# CPU.net
KiCad netlist of a schematic drawn in Altium Designer
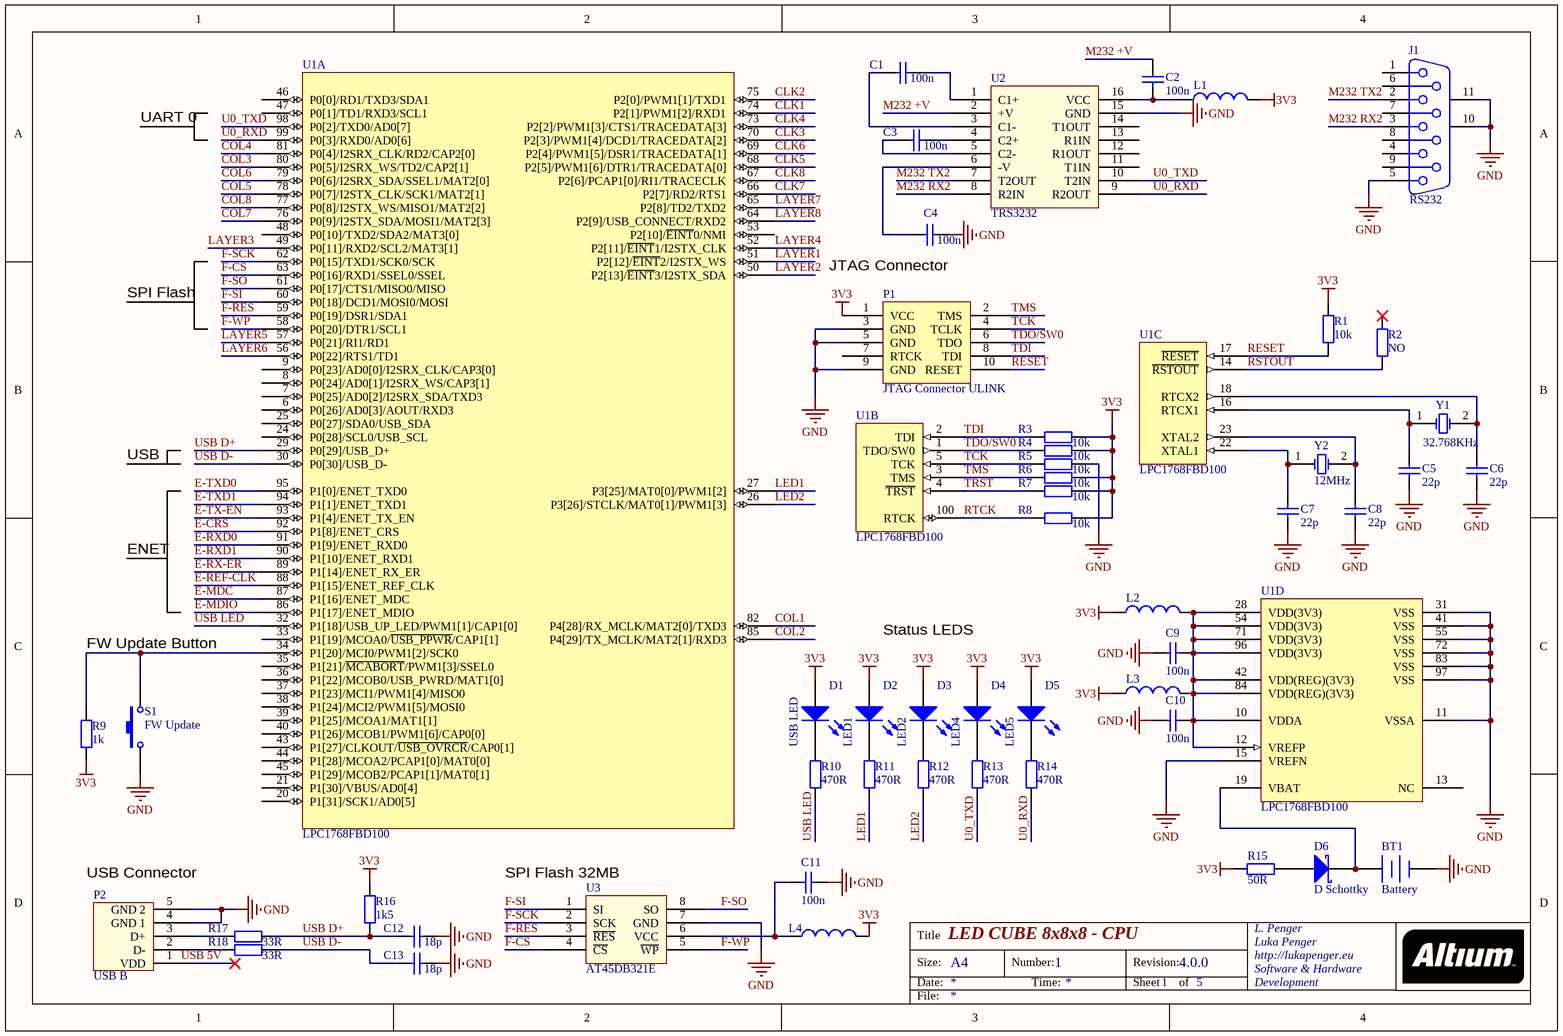
[diagram p0: CPU.SchDoc]

(export (version "E")
  (design (tool "Eeschema 10.0.6"))
  (components
    (comp (ref "BT1")
      (value "Battery")
      (footprint "Battery capacitor")
      (description "Multicell Battery")
      (fields (field (name "PUBLISHER") "Altium Limited"))
      (libsource (lib "Miscellaneous Devices") (part "Battery"))
    )
    (comp (ref "C1")
      (value "100n")
      (footprint "1608[0603]")
      (description "Capacitor")
      (fields (field (name "PUBLISHER") "Altium Limited"))
      (libsource (lib "Miscellaneous Devices") (part "Cap"))
    )
    (comp (ref "C2")
      (value "100n")
      (footprint "1608[0603]")
      (description "Capacitor")
      (fields (field (name "PUBLISHER") "Altium Limited"))
      (libsource (lib "Miscellaneous Devices") (part "Cap"))
    )
    (comp (ref "C3")
      (value "100n")
      (footprint "1608[0603]")
      (description "Capacitor")
      (fields (field (name "PUBLISHER") "Altium Limited"))
      (libsource (lib "Miscellaneous Devices") (part "Cap"))
    )
    (comp (ref "C4")
      (value "100n")
      (footprint "1608[0603]")
      (description "Capacitor")
      (fields (field (name "PUBLISHER") "Altium Limited"))
      (libsource (lib "Miscellaneous Devices") (part "Cap"))
    )
    (comp (ref "C5")
      (value "22p")
      (footprint "1608[0603]")
      (description "Capacitor")
      (fields (field (name "PUBLISHER") "Altium Limited"))
      (libsource (lib "Miscellaneous Devices") (part "Cap"))
    )
    (comp (ref "C6")
      (value "22p")
      (footprint "1608[0603]")
      (description "Capacitor")
      (fields (field (name "PUBLISHER") "Altium Limited"))
      (libsource (lib "Miscellaneous Devices") (part "Cap"))
    )
    (comp (ref "C7")
      (value "22p")
      (footprint "1608[0603]")
      (description "Capacitor")
      (fields (field (name "PUBLISHER") "Altium Limited"))
      (libsource (lib "Miscellaneous Devices") (part "Cap"))
    )
    (comp (ref "C8")
      (value "22p")
      (footprint "1608[0603]")
      (description "Capacitor")
      (fields (field (name "PUBLISHER") "Altium Limited"))
      (libsource (lib "Miscellaneous Devices") (part "Cap"))
    )
    (comp (ref "C9")
      (value "100n")
      (footprint "1608[0603]")
      (description "Capacitor")
      (fields (field (name "PUBLISHER") "Altium Limited"))
      (libsource (lib "Miscellaneous Devices") (part "Cap"))
    )
    (comp (ref "C10")
      (value "100n")
      (footprint "1608[0603]")
      (description "Capacitor")
      (fields (field (name "PUBLISHER") "Altium Limited"))
      (libsource (lib "Miscellaneous Devices") (part "Cap"))
    )
    (comp (ref "C11")
      (value "100n")
      (footprint "1608[0603]")
      (description "Capacitor")
      (fields (field (name "PUBLISHER") "Altium Limited"))
      (libsource (lib "Miscellaneous Devices") (part "Cap"))
    )
    (comp (ref "C12")
      (value "18p")
      (footprint "1608[0603]")
      (description "Capacitor")
      (fields (field (name "PUBLISHER") "Altium Limited"))
      (libsource (lib "Miscellaneous Devices") (part "Cap"))
    )
    (comp (ref "C13")
      (value "18p")
      (footprint "1608[0603]")
      (description "Capacitor")
      (fields (field (name "PUBLISHER") "Altium Limited"))
      (libsource (lib "Miscellaneous Devices") (part "Cap"))
    )
    (comp (ref "D1")
      (value "USB LED")
      (footprint "LED-1")
      (description "Typical INFRARED GaAs LED")
      (fields (field (name "PUBLISHER") "Altium Limited"))
      (libsource (lib "Miscellaneous Devices") (part "LED0"))
    )
    (comp (ref "D2")
      (value "LED1")
      (footprint "LED-1")
      (description "Typical INFRARED GaAs LED")
      (fields (field (name "PUBLISHER") "Altium Limited"))
      (libsource (lib "Miscellaneous Devices") (part "LED0"))
    )
    (comp (ref "D3")
      (value "LED2")
      (footprint "LED-1")
      (description "Typical INFRARED GaAs LED")
      (fields (field (name "PUBLISHER") "Altium Limited"))
      (libsource (lib "Miscellaneous Devices") (part "LED0"))
    )
    (comp (ref "D4")
      (value "LED4")
      (footprint "LED-1")
      (description "Typical INFRARED GaAs LED")
      (fields (field (name "PUBLISHER") "Altium Limited"))
      (libsource (lib "Miscellaneous Devices") (part "LED0"))
    )
    (comp (ref "D5")
      (value "LED5")
      (footprint "LED-1")
      (description "Typical INFRARED GaAs LED")
      (fields (field (name "PUBLISHER") "Altium Limited"))
      (libsource (lib "Miscellaneous Devices") (part "LED0"))
    )
    (comp (ref "D6")
      (value "D Schottky")
      (footprint "SMB")
      (description "Schottky Diode")
      (fields (field (name "PUBLISHER") "Altium Limited"))
      (libsource (lib "Miscellaneous Devices") (part "D Schottky"))
    )
    (comp (ref "J1")
      (value "RS232")
      (footprint "DSUB1.385-2H9")
      (description "Receptacle Assembly, 9 Position, Right Angle")
      (fields (field (name "PUBLISHER") "Altium Limited"))
      (libsource (lib "Miscellaneous Connectors") (part "D Connector 9"))
    )
    (comp (ref "L1")
      (value "Inductor")
      (footprint "1608[0603]")
      (fields (field (name "PUBLISHER") "Altium Limited"))
      (libsource (lib "Miscellaneous Devices") (part "Inductor"))
    )
    (comp (ref "L2")
      (value "Inductor")
      (footprint "1608[0603]")
      (fields (field (name "PUBLISHER") "Altium Limited"))
      (libsource (lib "Miscellaneous Devices") (part "Inductor"))
    )
    (comp (ref "L3")
      (value "Inductor")
      (footprint "1608[0603]")
      (fields (field (name "PUBLISHER") "Altium Limited"))
      (libsource (lib "Miscellaneous Devices") (part "Inductor"))
    )
    (comp (ref "L4")
      (value "Inductor")
      (footprint "1608[0603]")
      (fields (field (name "PUBLISHER") "Altium Limited"))
      (libsource (lib "Miscellaneous Devices") (part "Inductor"))
    )
    (comp (ref "P1")
      (value "JTAG Connector ULINK")
      (footprint "JTAG Connector ULINK")
      (description "JTAG Connector")
      (libsource (lib "LP_Lib") (part "JTAG Connector ULINK"))
    )
    (comp (ref "P2")
      (value "USB B")
      (footprint "USB B")
      (description "USB Connector")
      (libsource (lib "LP_Lib") (part "USB B"))
    )
    (comp (ref "R1")
      (value "10k")
      (footprint "1608[0603]")
      (description "Resistor")
      (fields (field (name "PUBLISHER") "Altium Limited"))
      (libsource (lib "Miscellaneous Devices") (part "Res2"))
    )
    (comp (ref "R2")
      (value "NO")
      (footprint "1608[0603]")
      (description "Resistor")
      (fields (field (name "PUBLISHER") "Altium Limited"))
      (libsource (lib "Miscellaneous Devices") (part "Res2"))
    )
    (comp (ref "R3")
      (value "10k")
      (footprint "1608[0603]")
      (description "Resistor")
      (fields (field (name "PUBLISHER") "Altium Limited"))
      (libsource (lib "") (part "Res2_3"))
    )
    (comp (ref "R4")
      (value "10k")
      (footprint "1608[0603]")
      (description "Resistor")
      (fields (field (name "PUBLISHER") "Altium Limited"))
      (libsource (lib "") (part "Res2_3"))
    )
    (comp (ref "R5")
      (value "10k")
      (footprint "1608[0603]")
      (description "Resistor")
      (fields (field (name "PUBLISHER") "Altium Limited"))
      (libsource (lib "") (part "Res2_3"))
    )
    (comp (ref "R6")
      (value "10k")
      (footprint "1608[0603]")
      (description "Resistor")
      (fields (field (name "PUBLISHER") "Altium Limited"))
      (libsource (lib "") (part "Res2_3"))
    )
    (comp (ref "R7")
      (value "10k")
      (footprint "1608[0603]")
      (description "Resistor")
      (fields (field (name "PUBLISHER") "Altium Limited"))
      (libsource (lib "") (part "Res2_3"))
    )
    (comp (ref "R8")
      (value "10k")
      (footprint "1608[0603]")
      (description "Resistor")
      (fields (field (name "PUBLISHER") "Altium Limited"))
      (libsource (lib "") (part "Res2_3"))
    )
    (comp (ref "R9")
      (value "1k")
      (footprint "1608[0603]")
      (description "Resistor")
      (fields (field (name "PUBLISHER") "Altium Limited"))
      (libsource (lib "Miscellaneous Devices") (part "Res2"))
    )
    (comp (ref "R10")
      (value "470R")
      (footprint "1608[0603]")
      (description "Resistor")
      (fields (field (name "PUBLISHER") "Altium Limited"))
      (libsource (lib "Miscellaneous Devices") (part "Res2"))
    )
    (comp (ref "R11")
      (value "470R")
      (footprint "1608[0603]")
      (description "Resistor")
      (fields (field (name "PUBLISHER") "Altium Limited"))
      (libsource (lib "Miscellaneous Devices") (part "Res2"))
    )
    (comp (ref "R12")
      (value "470R")
      (footprint "1608[0603]")
      (description "Resistor")
      (fields (field (name "PUBLISHER") "Altium Limited"))
      (libsource (lib "Miscellaneous Devices") (part "Res2"))
    )
    (comp (ref "R13")
      (value "470R")
      (footprint "1608[0603]")
      (description "Resistor")
      (fields (field (name "PUBLISHER") "Altium Limited"))
      (libsource (lib "Miscellaneous Devices") (part "Res2"))
    )
    (comp (ref "R14")
      (value "470R")
      (footprint "1608[0603]")
      (description "Resistor")
      (fields (field (name "PUBLISHER") "Altium Limited"))
      (libsource (lib "Miscellaneous Devices") (part "Res2"))
    )
    (comp (ref "R15")
      (value "50R")
      (footprint "6-0805_N")
      (description "Resistor")
      (fields (field (name "PUBLISHER") "Altium Limited"))
      (libsource (lib "") (part "Res2_1"))
    )
    (comp (ref "R16")
      (value "1k5")
      (footprint "1608[0603]")
      (description "Resistor")
      (fields (field (name "PUBLISHER") "Altium Limited"))
      (libsource (lib "") (part "Res2_2"))
    )
    (comp (ref "R17")
      (value "33R")
      (footprint "1608[0603]")
      (description "Resistor")
      (fields (field (name "PUBLISHER") "Altium Limited"))
      (libsource (lib "") (part "Res2_1"))
    )
    (comp (ref "R18")
      (value "33R")
      (footprint "1608[0603]")
      (description "Resistor")
      (fields (field (name "PUBLISHER") "Altium Limited"))
      (libsource (lib "") (part "Res2_1"))
    )
    (comp (ref "S1")
      (value "FW Update")
      (footprint "SWITCH-TACTILE-90")
      (description "Switch")
      (fields (field (name "PUBLISHER") "Altium Limited"))
      (libsource (lib "Miscellaneous Devices") (part "SW-PB"))
    )
    (comp (ref "U1")
      (value "LPC1768FBD100")
      (footprint "SOT407-1_N")
      (fields (field (name "PUBLISHER") "Altium Limited"))
      (libsource (lib "NXP LPC1768") (part "LPC1768FBD100"))
    )
    (comp (ref "U2")
      (value "TRS3232")
      (footprint "SOIC16_N")
      (description "Dual 232 +3V3")
      (libsource (lib "LP_Lib") (part "MAX2232"))
    )
    (comp (ref "U3")
      (value "AT45DB321E")
      (footprint "AT45DB321D")
      (description "SPI Flash 32MB")
      (libsource (lib "LP_Lib") (part "AT45DB321D"))
    )
    (comp (ref "Y1")
      (value "32.768KHz")
      (footprint "Crystal 4.1x1.5")
      (description "Crystal Oscillator")
      (fields (field (name "PUBLISHER") "Altium Limited"))
      (libsource (lib "Miscellaneous Devices") (part "XTAL"))
    )
    (comp (ref "Y2")
      (value "12MHz")
      (footprint "5x3.2 Crystal")
      (description "Crystal Oscillator")
      (fields (field (name "PUBLISHER") "Altium Limited"))
      (libsource (lib "Miscellaneous Devices") (part "XTAL"))
    )
  )
  (nets
    (net (code "1") (name "/CLK1") (class "Default")
      (node (ref "U1") (pin "74") (pinfunction "P2[1]/PWM1[2]/RXD1_74") (pintype "bidirectional"))
    )
    (net (code "2") (name "/CLK2") (class "Default")
      (node (ref "U1") (pin "75") (pinfunction "P2[0]/PWM1[1]/TXD1_75") (pintype "bidirectional"))
    )
    (net (code "3") (name "/CLK3") (class "Default")
      (node (ref "U1") (pin "70") (pinfunction "P2[3]/PWM1[4]/DCD1/TRACEDATA[2]_70") (pintype "bidirectional"))
    )
    (net (code "4") (name "/CLK4") (class "Default")
      (node (ref "U1") (pin "73") (pinfunction "P2[2]/PWM1[3]/CTS1/TRACEDATA[3]_73") (pintype "bidirectional"))
    )
    (net (code "5") (name "/CLK5") (class "Default")
      (node (ref "U1") (pin "68") (pinfunction "P2[5]/PWM1[6]/DTR1/TRACEDATA[0]_68") (pintype "bidirectional"))
    )
    (net (code "6") (name "/CLK6") (class "Default")
      (node (ref "U1") (pin "69") (pinfunction "P2[4]/PWM1[5]/DSR1/TRACEDATA[1]_69") (pintype "bidirectional"))
    )
    (net (code "7") (name "/CLK7") (class "Default")
      (node (ref "U1") (pin "66") (pinfunction "P2[7]/RD2/RTS1_66") (pintype "bidirectional"))
    )
    (net (code "8") (name "/CLK8") (class "Default")
      (node (ref "U1") (pin "67") (pinfunction "P2[6]/PCAP1[0]/RI1/TRACECLK_67") (pintype "bidirectional"))
    )
    (net (code "9") (name "/COL1") (class "Default")
      (node (ref "U1") (pin "82") (pinfunction "P4[28]/RX_MCLK/MAT2[0]/TXD3_82") (pintype "bidirectional"))
    )
    (net (code "10") (name "/COL2") (class "Default")
      (node (ref "U1") (pin "85") (pinfunction "P4[29]/TX_MCLK/MAT2[1]/RXD3_85") (pintype "bidirectional"))
    )
    (net (code "11") (name "/COL3") (class "Default")
      (node (ref "U1") (pin "80") (pinfunction "P0[5]/I2SRX_WS/TD2/CAP2[1]_80") (pintype "bidirectional"))
    )
    (net (code "12") (name "/COL4") (class "Default")
      (node (ref "U1") (pin "81") (pinfunction "P0[4]/I2SRX_CLK/RD2/CAP2[0]_81") (pintype "bidirectional"))
    )
    (net (code "13") (name "/COL5") (class "Default")
      (node (ref "U1") (pin "78") (pinfunction "P0[7]/I2STX_CLK/SCK1/MAT2[1]_78") (pintype "bidirectional"))
    )
    (net (code "14") (name "/COL6") (class "Default")
      (node (ref "U1") (pin "79") (pinfunction "P0[6]/I2SRX_SDA/SSEL1/MAT2[0]_79") (pintype "bidirectional"))
    )
    (net (code "15") (name "/COL7") (class "Default")
      (node (ref "U1") (pin "76") (pinfunction "P0[9]/I2STX_SDA/MOSI1/MAT2[3]_76") (pintype "bidirectional"))
    )
    (net (code "16") (name "/COL8") (class "Default")
      (node (ref "U1") (pin "77") (pinfunction "P0[8]/I2STX_WS/MISO1/MAT2[2]_77") (pintype "bidirectional"))
    )
    (net (code "17") (name "/E-CRS") (class "Default")
      (node (ref "U1") (pin "92") (pinfunction "P1[8]/ENET_CRS_92") (pintype "bidirectional"))
    )
    (net (code "18") (name "/E-MDC") (class "Default")
      (node (ref "U1") (pin "87") (pinfunction "P1[16]/ENET_MDC_87") (pintype "bidirectional"))
    )
    (net (code "19") (name "/E-MDIO") (class "Default")
      (node (ref "U1") (pin "86") (pinfunction "P1[17]/ENET_MDIO_86") (pintype "bidirectional"))
    )
    (net (code "20") (name "/E-REF-CLK") (class "Default")
      (node (ref "U1") (pin "88") (pinfunction "P1[15]/ENET_REF_CLK_88") (pintype "bidirectional"))
    )
    (net (code "21") (name "/E-RX-ER") (class "Default")
      (node (ref "U1") (pin "89") (pinfunction "P1[14]/ENET_RX_ER_89") (pintype "bidirectional"))
    )
    (net (code "22") (name "/E-RXD0") (class "Default")
      (node (ref "U1") (pin "91") (pinfunction "P1[9]/ENET_RXD0_91") (pintype "bidirectional"))
    )
    (net (code "23") (name "/E-RXD1") (class "Default")
      (node (ref "U1") (pin "90") (pinfunction "P1[10]/ENET_RXD1_90") (pintype "bidirectional"))
    )
    (net (code "24") (name "/E-TX-EN") (class "Default")
      (node (ref "U1") (pin "93") (pinfunction "P1[4]/ENET_TX_EN_93") (pintype "bidirectional"))
    )
    (net (code "25") (name "/E-TXD0") (class "Default")
      (node (ref "U1") (pin "95") (pinfunction "P1[0]/ENET_TXD0_95") (pintype "bidirectional"))
    )
    (net (code "26") (name "/E-TXD1") (class "Default")
      (node (ref "U1") (pin "94") (pinfunction "P1[1]/ENET_TXD1_94") (pintype "bidirectional"))
    )
    (net (code "27") (name "/F-CS") (class "Default")
      (node (ref "U1") (pin "63") (pinfunction "P0[16]/RXD1/SSEL0/SSEL_63") (pintype "bidirectional"))
      (node (ref "U3") (pin "4") (pinfunction "~{CS}_4") (pintype "passive"))
    )
    (net (code "28") (name "/F-RES") (class "Default")
      (node (ref "U1") (pin "59") (pinfunction "P0[19]/DSR1/SDA1_59") (pintype "bidirectional"))
      (node (ref "U3") (pin "3") (pinfunction "~{RES}_3") (pintype "passive"))
    )
    (net (code "29") (name "/F-SCK") (class "Default")
      (node (ref "U1") (pin "62") (pinfunction "P0[15]/TXD1/SCK0/SCK_62") (pintype "bidirectional"))
      (node (ref "U3") (pin "2") (pinfunction "SCK_2") (pintype "passive"))
    )
    (net (code "30") (name "/F-SI") (class "Default")
      (node (ref "U1") (pin "60") (pinfunction "P0[18]/DCD1/MOSI0/MOSI_60") (pintype "bidirectional"))
      (node (ref "U3") (pin "1") (pinfunction "SI_1") (pintype "passive"))
    )
    (net (code "31") (name "/F-SO") (class "Default")
      (node (ref "U1") (pin "61") (pinfunction "P0[17]/CTS1/MISO0/MISO_61") (pintype "bidirectional"))
      (node (ref "U3") (pin "8") (pinfunction "SO_8") (pintype "passive"))
    )
    (net (code "32") (name "/F-WP") (class "Default")
      (node (ref "U1") (pin "58") (pinfunction "P0[20]/DTR1/SCL1_58") (pintype "bidirectional"))
      (node (ref "U3") (pin "5") (pinfunction "~{WP}_5") (pintype "passive"))
    )
    (net (code "33") (name "/LAYER1") (class "Default")
      (node (ref "U1") (pin "51") (pinfunction "P2[12]/~{EINT}2/I2STX_WS_51") (pintype "bidirectional"))
    )
    (net (code "34") (name "/LAYER2") (class "Default")
      (node (ref "U1") (pin "50") (pinfunction "P2[13]/~{EINT}3/I2STX_SDA_50") (pintype "bidirectional"))
    )
    (net (code "35") (name "/LAYER3") (class "Default")
      (node (ref "U1") (pin "49") (pinfunction "P0[11]/RXD2/SCL2/MAT3[1]_49") (pintype "bidirectional"))
    )
    (net (code "36") (name "/LAYER4") (class "Default")
      (node (ref "U1") (pin "52") (pinfunction "P2[11]/~{EINT}1/I2STX_CLK_52") (pintype "bidirectional"))
    )
    (net (code "37") (name "/LAYER5") (class "Default")
      (node (ref "U1") (pin "57") (pinfunction "P0[21]/RI1/RD1_57") (pintype "bidirectional"))
    )
    (net (code "38") (name "/LAYER6") (class "Default")
      (node (ref "U1") (pin "56") (pinfunction "P0[22]/RTS1/TD1_56") (pintype "bidirectional"))
    )
    (net (code "39") (name "/LAYER7") (class "Default")
      (node (ref "U1") (pin "65") (pinfunction "P2[8]/TD2/TXD2_65") (pintype "bidirectional"))
    )
    (net (code "40") (name "/LAYER8") (class "Default")
      (node (ref "U1") (pin "64") (pinfunction "P2[9]/USB_CONNECT/RXD2_64") (pintype "bidirectional"))
    )
    (net (code "41") (name "/LED1") (class "Default")
      (node (ref "R11") (pin "1") (pinfunction "1_1") (pintype "passive"))
      (node (ref "U1") (pin "27") (pinfunction "P3[25]/MAT0[0]/PWM1[2]_27") (pintype "bidirectional"))
    )
    (net (code "42") (name "/LED2") (class "Default")
      (node (ref "R12") (pin "1") (pinfunction "1_1") (pintype "passive"))
      (node (ref "U1") (pin "26") (pinfunction "P3[26]/STCLK/MAT0[1]/PWM1[3]_26") (pintype "bidirectional"))
    )
    (net (code "43") (name "/M232 +V") (class "Default")
      (node (ref "C2") (pin "1") (pinfunction "1_1") (pintype "passive"))
      (node (ref "U2") (pin "2") (pinfunction "+V_2") (pintype "passive"))
    )
    (net (code "44") (name "/M232 RX2") (class "Default")
      (node (ref "J1") (pin "3") (pinfunction "3_3") (pintype "passive"))
      (node (ref "U2") (pin "8") (pinfunction "R2IN_8") (pintype "passive"))
    )
    (net (code "45") (name "/M232 TX2") (class "Default")
      (node (ref "J1") (pin "2") (pinfunction "2_2") (pintype "passive"))
      (node (ref "U2") (pin "7") (pinfunction "T2OUT_7") (pintype "passive"))
    )
    (net (code "46") (name "/RESET") (class "Default")
      (node (ref "P1") (pin "10") (pinfunction "RESET_10") (pintype "passive"))
      (node (ref "R1") (pin "1") (pinfunction "1_1") (pintype "passive"))
      (node (ref "U1") (pin "17") (pinfunction "~{RESET}_17") (pintype "input"))
    )
    (net (code "47") (name "/RSTOUT") (class "Default")
      (node (ref "R2") (pin "1") (pinfunction "1_1") (pintype "passive"))
      (node (ref "U1") (pin "14") (pinfunction "~{RSTOUT}_14") (pintype "output"))
    )
    (net (code "48") (name "/RTCK") (class "Default")
      (node (ref "R8") (pin "1") (pinfunction "1_1") (pintype "passive"))
      (node (ref "U1") (pin "100") (pinfunction "RTCK_100") (pintype "bidirectional"))
    )
    (net (code "49") (name "/TCK") (class "Default")
      (node (ref "P1") (pin "4") (pinfunction "TCLK_4") (pintype "passive"))
      (node (ref "R5") (pin "1") (pinfunction "1_1") (pintype "passive"))
      (node (ref "U1") (pin "5") (pinfunction "TCK_5") (pintype "input"))
    )
    (net (code "50") (name "/TDI") (class "Default")
      (node (ref "P1") (pin "8") (pinfunction "TDI_8") (pintype "passive"))
      (node (ref "R3") (pin "1") (pinfunction "1_1") (pintype "passive"))
      (node (ref "U1") (pin "2") (pinfunction "TDI_2") (pintype "input"))
    )
    (net (code "51") (name "/TDO{slash}SW0") (class "Default")
      (node (ref "P1") (pin "6") (pinfunction "TDO_6") (pintype "passive"))
      (node (ref "R4") (pin "1") (pinfunction "1_1") (pintype "passive"))
      (node (ref "U1") (pin "1") (pinfunction "TDO/SW0_1") (pintype "output"))
    )
    (net (code "52") (name "/TMS") (class "Default")
      (node (ref "P1") (pin "2") (pinfunction "TMS_2") (pintype "passive"))
      (node (ref "R6") (pin "1") (pinfunction "1_1") (pintype "passive"))
      (node (ref "U1") (pin "3") (pinfunction "TMS_3") (pintype "input"))
    )
    (net (code "53") (name "/TRST") (class "Default")
      (node (ref "R7") (pin "1") (pinfunction "1_1") (pintype "passive"))
      (node (ref "U1") (pin "4") (pinfunction "~{TRST}_4") (pintype "input"))
    )
    (net (code "54") (name "/U0_RXD") (class "Default")
      (node (ref "R14") (pin "1") (pinfunction "1_1") (pintype "passive"))
      (node (ref "U1") (pin "99") (pinfunction "P0[3]/RXD0/AD0[6]_99") (pintype "bidirectional"))
      (node (ref "U2") (pin "9") (pinfunction "R2OUT_9") (pintype "passive"))
    )
    (net (code "55") (name "/U0_TXD") (class "Default")
      (node (ref "R13") (pin "1") (pinfunction "1_1") (pintype "passive"))
      (node (ref "U1") (pin "98") (pinfunction "P0[2]/TXD0/AD0[7]_98") (pintype "bidirectional"))
      (node (ref "U2") (pin "10") (pinfunction "T2IN_10") (pintype "passive"))
    )
    (net (code "57") (name "/USB D+") (class "Default")
      (node (ref "C12") (pin "1") (pinfunction "1_1") (pintype "passive"))
      (node (ref "R16") (pin "2") (pinfunction "2_2") (pintype "passive"))
      (node (ref "R17") (pin "1") (pinfunction "1_1") (pintype "passive"))
      (node (ref "U1") (pin "29") (pinfunction "P0[29]/USB_D+_29") (pintype "bidirectional"))
    )
    (net (code "58") (name "/USB D-") (class "Default")
      (node (ref "C13") (pin "1") (pinfunction "1_1") (pintype "passive"))
      (node (ref "R18") (pin "1") (pinfunction "1_1") (pintype "passive"))
      (node (ref "U1") (pin "30") (pinfunction "P0[30]/USB_D-_30") (pintype "bidirectional"))
    )
    (net (code "59") (name "/USB LED") (class "Default")
      (node (ref "R10") (pin "1") (pinfunction "1_1") (pintype "passive"))
      (node (ref "U1") (pin "32") (pinfunction "P1[18]/USB_UP_LED/PWM1[1]/CAP1[0]_32") (pintype "bidirectional"))
    )
    (net (code "60") (name "3V3") (class "Default")
      (node (ref "D1") (pin "1") (pinfunction "A_1") (pintype "passive"))
      (node (ref "D2") (pin "1") (pinfunction "A_1") (pintype "passive"))
      (node (ref "D3") (pin "1") (pinfunction "A_1") (pintype "passive"))
      (node (ref "D4") (pin "1") (pinfunction "A_1") (pintype "passive"))
      (node (ref "D5") (pin "1") (pinfunction "A_1") (pintype "passive"))
      (node (ref "L1") (pin "2") (pinfunction "2_2") (pintype "passive"))
      (node (ref "L2") (pin "1") (pinfunction "1_1") (pintype "passive"))
      (node (ref "L3") (pin "1") (pinfunction "1_1") (pintype "passive"))
      (node (ref "L4") (pin "2") (pinfunction "2_2") (pintype "passive"))
      (node (ref "P1") (pin "1") (pinfunction "VCC_1") (pintype "passive"))
      (node (ref "R1") (pin "2") (pinfunction "2_2") (pintype "passive"))
      (node (ref "R15") (pin "2") (pinfunction "2_2") (pintype "passive"))
      (node (ref "R16") (pin "1") (pinfunction "1_1") (pintype "passive"))
      (node (ref "R3") (pin "2") (pinfunction "2_2") (pintype "passive"))
      (node (ref "R4") (pin "2") (pinfunction "2_2") (pintype "passive"))
      (node (ref "R6") (pin "2") (pinfunction "2_2") (pintype "passive"))
      (node (ref "R7") (pin "2") (pinfunction "2_2") (pintype "passive"))
      (node (ref "R8") (pin "2") (pinfunction "2_2") (pintype "passive"))
      (node (ref "R9") (pin "1") (pinfunction "1_1") (pintype "passive"))
    )
    (net (code "61") (name "GND") (class "Default")
      (node (ref "BT1") (pin "2") (pinfunction "-_2") (pintype "passive"))
      (node (ref "C10") (pin "1") (pinfunction "1_1") (pintype "passive"))
      (node (ref "C11") (pin "1") (pinfunction "1_1") (pintype "passive"))
      (node (ref "C12") (pin "2") (pinfunction "2_2") (pintype "passive"))
      (node (ref "C13") (pin "2") (pinfunction "2_2") (pintype "passive"))
      (node (ref "C4") (pin "1") (pinfunction "1_1") (pintype "passive"))
      (node (ref "C5") (pin "1") (pinfunction "1_1") (pintype "passive"))
      (node (ref "C6") (pin "1") (pinfunction "1_1") (pintype "passive"))
      (node (ref "C7") (pin "1") (pinfunction "1_1") (pintype "passive"))
      (node (ref "C8") (pin "1") (pinfunction "1_1") (pintype "passive"))
      (node (ref "C9") (pin "2") (pinfunction "2_2") (pintype "passive"))
      (node (ref "J1") (pin "10") (pinfunction "MH1_10") (pintype "passive"))
      (node (ref "J1") (pin "11") (pinfunction "MH2_11") (pintype "passive"))
      (node (ref "J1") (pin "5") (pinfunction "5_5") (pintype "passive"))
      (node (ref "P1") (pin "3") (pinfunction "GND_3") (pintype "passive"))
      (node (ref "P1") (pin "5") (pinfunction "GND_5") (pintype "passive"))
      (node (ref "P1") (pin "9") (pinfunction "GND_9") (pintype "passive"))
      (node (ref "P2") (pin "4") (pinfunction "GND_1_4") (pintype "passive"))
      (node (ref "P2") (pin "5") (pinfunction "GND_2_5") (pintype "passive"))
      (node (ref "R5") (pin "2") (pinfunction "2_2") (pintype "passive"))
      (node (ref "S1") (pin "1") (pinfunction "1_1") (pintype "passive"))
      (node (ref "U1") (pin "11") (pinfunction "VSSA_11") (pintype "power_in"))
      (node (ref "U1") (pin "15") (pinfunction "VREFN_15") (pintype "power_in"))
      (node (ref "U1") (pin "31") (pinfunction "VSS_31") (pintype "power_in"))
      (node (ref "U1") (pin "41") (pinfunction "VSS_41") (pintype "power_in"))
      (node (ref "U1") (pin "55") (pinfunction "VSS_55") (pintype "power_in"))
      (node (ref "U1") (pin "72") (pinfunction "VSS_72") (pintype "power_in"))
      (node (ref "U1") (pin "83") (pinfunction "VSS_83") (pintype "power_in"))
      (node (ref "U1") (pin "97") (pinfunction "VSS_97") (pintype "power_in"))
      (node (ref "U2") (pin "15") (pinfunction "GND_15") (pintype "passive"))
      (node (ref "U3") (pin "7") (pinfunction "GND_7") (pintype "passive"))
    )
    (net (code "62") (name "Net-(BT1-+)") (class "Default")
      (node (ref "BT1") (pin "1") (pinfunction "+_1") (pintype "passive"))
      (node (ref "D6") (pin "2") (pinfunction "K_2") (pintype "passive"))
      (node (ref "U1") (pin "19") (pinfunction "VBAT_19") (pintype "power_in"))
    )
    (net (code "63") (name "Net-(D1-K)") (class "Default")
      (node (ref "D1") (pin "2") (pinfunction "K_2") (pintype "passive"))
      (node (ref "R10") (pin "2") (pinfunction "2_2") (pintype "passive"))
    )
    (net (code "64") (name "Net-(D2-K)") (class "Default")
      (node (ref "D2") (pin "2") (pinfunction "K_2") (pintype "passive"))
      (node (ref "R11") (pin "2") (pinfunction "2_2") (pintype "passive"))
    )
    (net (code "65") (name "Net-(D3-K)") (class "Default")
      (node (ref "D3") (pin "2") (pinfunction "K_2") (pintype "passive"))
      (node (ref "R12") (pin "2") (pinfunction "2_2") (pintype "passive"))
    )
    (net (code "66") (name "Net-(D4-K)") (class "Default")
      (node (ref "D4") (pin "2") (pinfunction "K_2") (pintype "passive"))
      (node (ref "R13") (pin "2") (pinfunction "2_2") (pintype "passive"))
    )
    (net (code "67") (name "Net-(D5-K)") (class "Default")
      (node (ref "D5") (pin "2") (pinfunction "K_2") (pintype "passive"))
      (node (ref "R14") (pin "2") (pinfunction "2_2") (pintype "passive"))
    )
    (net (code "68") (name "Net-(D6-A)") (class "Default")
      (node (ref "D6") (pin "1") (pinfunction "A_1") (pintype "passive"))
      (node (ref "R15") (pin "1") (pinfunction "1_1") (pintype "passive"))
    )
    (net (code "69") (name "Net-(P2-D+)") (class "Default")
      (node (ref "P2") (pin "3") (pinfunction "D+_3") (pintype "passive"))
      (node (ref "R17") (pin "2") (pinfunction "2_2") (pintype "passive"))
    )
    (net (code "70") (name "Net-(P2-D-)") (class "Default")
      (node (ref "P2") (pin "2") (pinfunction "D-_2") (pintype "passive"))
      (node (ref "R18") (pin "2") (pinfunction "2_2") (pintype "passive"))
    )
    (net (code "71") (name "Net-(U1A-P1[20]{slash}MCI0{slash}PWM1[2]{slash}SCK0)") (class "Default")
      (node (ref "R9") (pin "2") (pinfunction "2_2") (pintype "passive"))
      (node (ref "S1") (pin "2") (pinfunction "2_2") (pintype "passive"))
      (node (ref "U1") (pin "34") (pinfunction "P1[20]/MCI0/PWM1[2]/SCK0_34") (pintype "bidirectional"))
    )
    (net (code "72") (name "Net-(U1C-RTCX1)") (class "Default")
      (node (ref "C5") (pin "2") (pinfunction "2_2") (pintype "passive"))
      (node (ref "U1") (pin "16") (pinfunction "RTCX1_16") (pintype "input"))
      (node (ref "Y1") (pin "1") (pinfunction "OSC1_1") (pintype "passive"))
    )
    (net (code "73") (name "Net-(U1C-RTCX2)") (class "Default")
      (node (ref "C6") (pin "2") (pinfunction "2_2") (pintype "passive"))
      (node (ref "U1") (pin "18") (pinfunction "RTCX2_18") (pintype "output"))
      (node (ref "Y1") (pin "2") (pinfunction "OSC2_2") (pintype "passive"))
    )
    (net (code "74") (name "Net-(U1C-XTAL1)") (class "Default")
      (node (ref "C7") (pin "2") (pinfunction "2_2") (pintype "passive"))
      (node (ref "U1") (pin "22") (pinfunction "XTAL1_22") (pintype "input"))
      (node (ref "Y2") (pin "1") (pinfunction "OSC1_1") (pintype "passive"))
    )
    (net (code "75") (name "Net-(U1C-XTAL2)") (class "Default")
      (node (ref "C8") (pin "2") (pinfunction "2_2") (pintype "passive"))
      (node (ref "U1") (pin "23") (pinfunction "XTAL2_23") (pintype "output"))
      (node (ref "Y2") (pin "2") (pinfunction "OSC2_2") (pintype "passive"))
    )
    (net (code "76") (name "Net-(U1D-VDDA)") (class "Default")
      (node (ref "C10") (pin "2") (pinfunction "2_2") (pintype "passive"))
      (node (ref "C9") (pin "1") (pinfunction "1_1") (pintype "passive"))
      (node (ref "L2") (pin "2") (pinfunction "2_2") (pintype "passive"))
      (node (ref "L3") (pin "2") (pinfunction "2_2") (pintype "passive"))
      (node (ref "U1") (pin "10") (pinfunction "VDDA_10") (pintype "power_in"))
      (node (ref "U1") (pin "12") (pinfunction "VREFP_12") (pintype "input"))
      (node (ref "U1") (pin "28") (pinfunction "VDD(3V3)_28") (pintype "power_in"))
      (node (ref "U1") (pin "42") (pinfunction "VDD(REG)(3V3)_42") (pintype "power_in"))
      (node (ref "U1") (pin "54") (pinfunction "VDD(3V3)_54") (pintype "power_in"))
      (node (ref "U1") (pin "71") (pinfunction "VDD(3V3)_71") (pintype "power_in"))
      (node (ref "U1") (pin "84") (pinfunction "VDD(REG)(3V3)_84") (pintype "power_in"))
      (node (ref "U1") (pin "96") (pinfunction "VDD(3V3)_96") (pintype "power_in"))
    )
    (net (code "77") (name "Net-(U2--V)") (class "Default")
      (node (ref "C4") (pin "2") (pinfunction "2_2") (pintype "passive"))
      (node (ref "U2") (pin "6") (pinfunction "-V_6") (pintype "passive"))
    )
    (net (code "78") (name "Net-(U2-C1+)") (class "Default")
      (node (ref "C1") (pin "2") (pinfunction "2_2") (pintype "passive"))
      (node (ref "U2") (pin "1") (pinfunction "C1+_1") (pintype "passive"))
    )
    (net (code "79") (name "Net-(U2-C1-)") (class "Default")
      (node (ref "C1") (pin "1") (pinfunction "1_1") (pintype "passive"))
      (node (ref "U2") (pin "3") (pinfunction "C1-_3") (pintype "passive"))
    )
    (net (code "80") (name "Net-(U2-C2+)") (class "Default")
      (node (ref "C3") (pin "2") (pinfunction "2_2") (pintype "passive"))
      (node (ref "U2") (pin "4") (pinfunction "C2+_4") (pintype "passive"))
    )
    (net (code "81") (name "Net-(U2-C2-)") (class "Default")
      (node (ref "C3") (pin "1") (pinfunction "1_1") (pintype "passive"))
      (node (ref "U2") (pin "5") (pinfunction "C2-_5") (pintype "passive"))
    )
    (net (code "82") (name "Net-(U2-VCC)") (class "Default")
      (node (ref "C2") (pin "2") (pinfunction "2_2") (pintype "passive"))
      (node (ref "L1") (pin "1") (pinfunction "1_1") (pintype "passive"))
      (node (ref "U2") (pin "16") (pinfunction "VCC_16") (pintype "passive"))
    )
    (net (code "83") (name "Net-(U3-VCC)") (class "Default")
      (node (ref "C11") (pin "2") (pinfunction "2_2") (pintype "passive"))
      (node (ref "L4") (pin "1") (pinfunction "1_1") (pintype "passive"))
      (node (ref "U3") (pin "6") (pinfunction "VCC_6") (pintype "passive"))
    )
    (net (code "84") (name "unconnected-(J1-Pad1)") (class "Default")
      (node (ref "J1") (pin "1") (pinfunction "1_1") (pintype "passive"))
    )
    (net (code "85") (name "unconnected-(J1-Pad4)") (class "Default")
      (node (ref "J1") (pin "4") (pinfunction "4_4") (pintype "passive"))
    )
    (net (code "86") (name "unconnected-(J1-Pad6)") (class "Default")
      (node (ref "J1") (pin "6") (pinfunction "6_6") (pintype "passive"))
    )
    (net (code "87") (name "unconnected-(J1-Pad7)") (class "Default")
      (node (ref "J1") (pin "7") (pinfunction "7_7") (pintype "passive"))
    )
    (net (code "88") (name "unconnected-(J1-Pad8)") (class "Default")
      (node (ref "J1") (pin "8") (pinfunction "8_8") (pintype "passive"))
    )
    (net (code "89") (name "unconnected-(J1-Pad9)") (class "Default")
      (node (ref "J1") (pin "9") (pinfunction "9_9") (pintype "passive"))
    )
    (net (code "90") (name "unconnected-(P1-RTCK-Pad7)") (class "Default")
      (node (ref "P1") (pin "7") (pinfunction "RTCK_7") (pintype "passive"))
    )
    (net (code "91") (name "unconnected-(P2-VDD-Pad1)") (class "Default")
      (node (ref "P2") (pin "1") (pinfunction "VDD_1") (pintype "passive+no_connect"))
    )
    (net (code "92") (name "unconnected-(R2-Pad2)") (class "Default")
      (node (ref "R2") (pin "2") (pinfunction "2_2") (pintype "passive+no_connect"))
    )
    (net (code "93") (name "unconnected-(U1A-P0[0]{slash}RD1{slash}TXD3{slash}SDA1-Pad46)") (class "Default")
      (node (ref "U1") (pin "46") (pinfunction "P0[0]/RD1/TXD3/SDA1_46") (pintype "bidirectional"))
    )
    (net (code "94") (name "unconnected-(U1A-P0[1]{slash}TD1{slash}RXD3{slash}SCL1-Pad47)") (class "Default")
      (node (ref "U1") (pin "47") (pinfunction "P0[1]/TD1/RXD3/SCL1_47") (pintype "bidirectional"))
    )
    (net (code "95") (name "unconnected-(U1A-P0[10]{slash}TXD2{slash}SDA2{slash}MAT3[0]-Pad48)") (class "Default")
      (node (ref "U1") (pin "48") (pinfunction "P0[10]/TXD2/SDA2/MAT3[0]_48") (pintype "bidirectional"))
    )
    (net (code "96") (name "unconnected-(U1A-P0[23]{slash}AD0[0]{slash}I2SRX_CLK{slash}CAP3[0]-Pad9)") (class "Default")
      (node (ref "U1") (pin "9") (pinfunction "P0[23]/AD0[0]/I2SRX_CLK/CAP3[0]_9") (pintype "bidirectional"))
    )
    (net (code "97") (name "unconnected-(U1A-P0[24]{slash}AD0[1]{slash}I2SRX_WS{slash}CAP3[1]-Pad8)") (class "Default")
      (node (ref "U1") (pin "8") (pinfunction "P0[24]/AD0[1]/I2SRX_WS/CAP3[1]_8") (pintype "bidirectional"))
    )
    (net (code "98") (name "unconnected-(U1A-P0[25]{slash}AD0[2]{slash}I2SRX_SDA{slash}TXD3-Pad7)") (class "Default")
      (node (ref "U1") (pin "7") (pinfunction "P0[25]/AD0[2]/I2SRX_SDA/TXD3_7") (pintype "bidirectional"))
    )
    (net (code "99") (name "unconnected-(U1A-P0[26]{slash}AD0[3]{slash}AOUT{slash}RXD3-Pad6)") (class "Default")
      (node (ref "U1") (pin "6") (pinfunction "P0[26]/AD0[3]/AOUT/RXD3_6") (pintype "bidirectional"))
    )
    (net (code "100") (name "unconnected-(U1A-P0[27]{slash}SDA0{slash}USB_SDA-Pad25)") (class "Default")
      (node (ref "U1") (pin "25") (pinfunction "P0[27]/SDA0/USB_SDA_25") (pintype "bidirectional"))
    )
    (net (code "101") (name "unconnected-(U1A-P0[28]{slash}SCL0{slash}USB_SCL-Pad24)") (class "Default")
      (node (ref "U1") (pin "24") (pinfunction "P0[28]/SCL0/USB_SCL_24") (pintype "bidirectional"))
    )
    (net (code "102") (name "unconnected-(U1A-P1[19]{slash}MCOA0{slash}~{USB_PPWR}{slash}CAP1[1]-Pad33)") (class "Default")
      (node (ref "U1") (pin "33") (pinfunction "P1[19]/MCOA0/~{USB_PPWR}/CAP1[1]_33") (pintype "bidirectional"))
    )
    (net (code "103") (name "unconnected-(U1A-P1[21]{slash}~{MCABORT}{slash}PWM1[3]{slash}SSEL0-Pad35)") (class "Default")
      (node (ref "U1") (pin "35") (pinfunction "P1[21]/~{MCABORT}/PWM1[3]/SSEL0_35") (pintype "bidirectional"))
    )
    (net (code "104") (name "unconnected-(U1A-P1[22]{slash}MCOB0{slash}USB_PWRD{slash}MAT1[0]-Pad36)") (class "Default")
      (node (ref "U1") (pin "36") (pinfunction "P1[22]/MCOB0/USB_PWRD/MAT1[0]_36") (pintype "bidirectional"))
    )
    (net (code "105") (name "unconnected-(U1A-P1[23]{slash}MCI1{slash}PWM1[4]{slash}MISO0-Pad37)") (class "Default")
      (node (ref "U1") (pin "37") (pinfunction "P1[23]/MCI1/PWM1[4]/MISO0_37") (pintype "bidirectional"))
    )
    (net (code "106") (name "unconnected-(U1A-P1[24]{slash}MCI2{slash}PWM1[5]{slash}MOSI0-Pad38)") (class "Default")
      (node (ref "U1") (pin "38") (pinfunction "P1[24]/MCI2/PWM1[5]/MOSI0_38") (pintype "bidirectional"))
    )
    (net (code "107") (name "unconnected-(U1A-P1[25]{slash}MCOA1{slash}MAT1[1]-Pad39)") (class "Default")
      (node (ref "U1") (pin "39") (pinfunction "P1[25]/MCOA1/MAT1[1]_39") (pintype "bidirectional"))
    )
    (net (code "108") (name "unconnected-(U1A-P1[26]{slash}MCOB1{slash}PWM1[6]{slash}CAP0[0]-Pad40)") (class "Default")
      (node (ref "U1") (pin "40") (pinfunction "P1[26]/MCOB1/PWM1[6]/CAP0[0]_40") (pintype "bidirectional"))
    )
    (net (code "109") (name "unconnected-(U1A-P1[27]{slash}CLKOUT{slash}~{USB_OVRCR}{slash}CAP0[1]-Pad43)") (class "Default")
      (node (ref "U1") (pin "43") (pinfunction "P1[27]/CLKOUT/~{USB_OVRCR}/CAP0[1]_43") (pintype "bidirectional"))
    )
    (net (code "110") (name "unconnected-(U1A-P1[28]{slash}MCOA2{slash}PCAP1[0]{slash}MAT0[0]-Pad44)") (class "Default")
      (node (ref "U1") (pin "44") (pinfunction "P1[28]/MCOA2/PCAP1[0]/MAT0[0]_44") (pintype "bidirectional"))
    )
    (net (code "111") (name "unconnected-(U1A-P1[29]{slash}MCOB2{slash}PCAP1[1]{slash}MAT0[1]-Pad45)") (class "Default")
      (node (ref "U1") (pin "45") (pinfunction "P1[29]/MCOB2/PCAP1[1]/MAT0[1]_45") (pintype "bidirectional"))
    )
    (net (code "112") (name "unconnected-(U1A-P1[30]{slash}VBUS{slash}AD0[4]-Pad21)") (class "Default")
      (node (ref "U1") (pin "21") (pinfunction "P1[30]/VBUS/AD0[4]_21") (pintype "bidirectional"))
    )
    (net (code "113") (name "unconnected-(U1A-P1[31]{slash}SCK1{slash}AD0[5]-Pad20)") (class "Default")
      (node (ref "U1") (pin "20") (pinfunction "P1[31]/SCK1/AD0[5]_20") (pintype "bidirectional"))
    )
    (net (code "114") (name "unconnected-(U1A-P2[10]{slash}~{EINT}0{slash}NMI-Pad53)") (class "Default")
      (node (ref "U1") (pin "53") (pinfunction "P2[10]/~{EINT}0/NMI_53") (pintype "bidirectional"))
    )
    (net (code "115") (name "unconnected-(U1D-NC-Pad13)") (class "Default")
      (node (ref "U1") (pin "13") (pinfunction "NC_13") (pintype "power_in"))
    )
    (net (code "116") (name "unconnected-(U2-R1IN-Pad13)") (class "Default")
      (node (ref "U2") (pin "13") (pinfunction "R1IN_13") (pintype "passive"))
    )
    (net (code "117") (name "unconnected-(U2-R1OUT-Pad12)") (class "Default")
      (node (ref "U2") (pin "12") (pinfunction "R1OUT_12") (pintype "passive"))
    )
    (net (code "118") (name "unconnected-(U2-T1IN-Pad11)") (class "Default")
      (node (ref "U2") (pin "11") (pinfunction "T1IN_11") (pintype "passive"))
    )
    (net (code "119") (name "unconnected-(U2-T1OUT-Pad14)") (class "Default")
      (node (ref "U2") (pin "14") (pinfunction "T1OUT_14") (pintype "passive"))
    )
  )
)
